# hitpoint.net
KiCad netlist of a schematic drawn in EAGLE
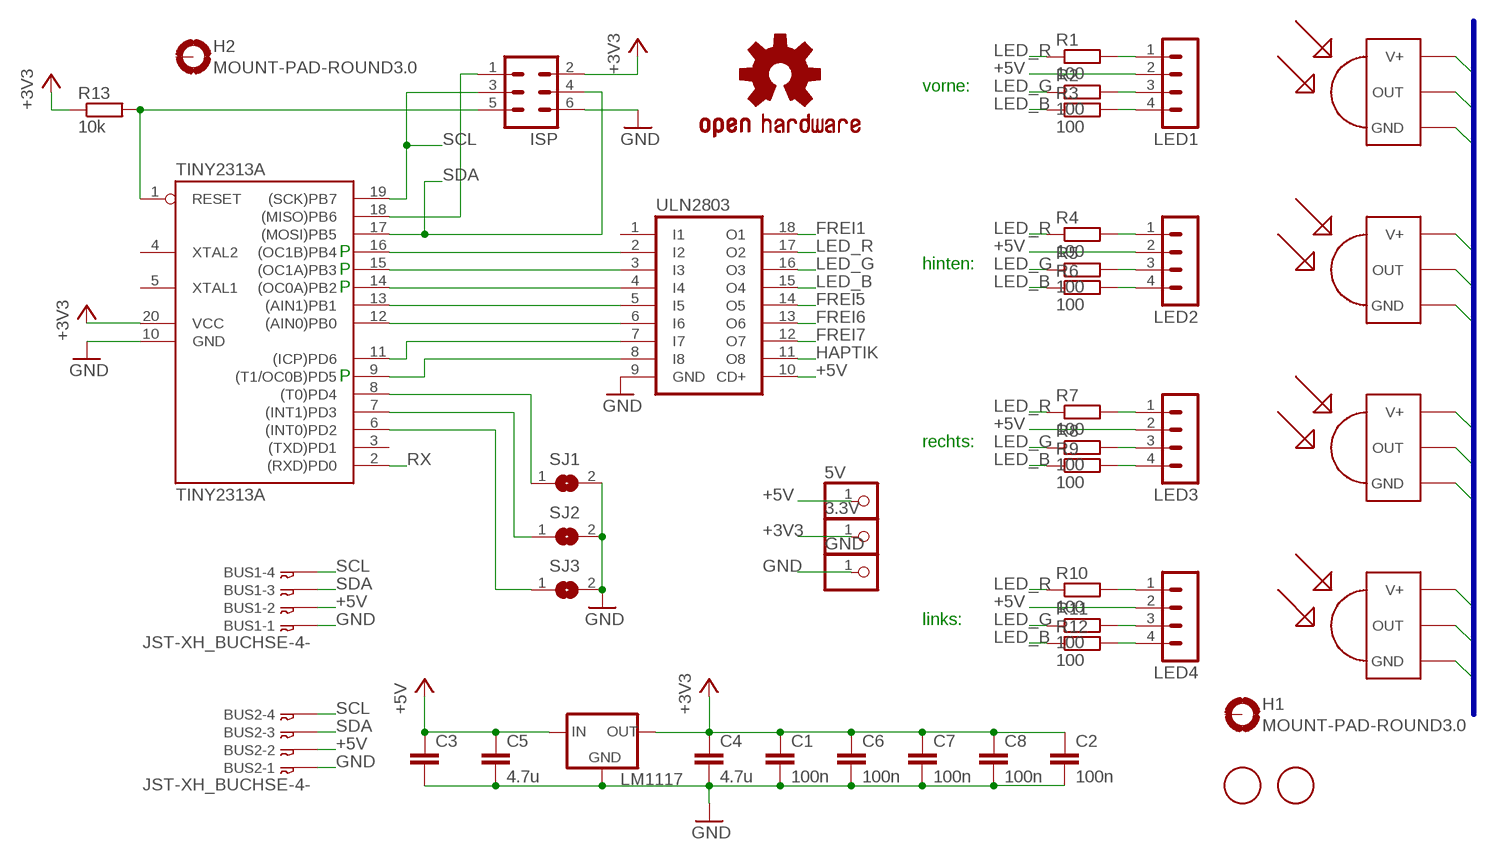
[diagram p0: schematic, sheet 1]

(export (version "E")
  (design (tool "Eeschema 10.0.6"))
  (components
    (comp (ref "3.3V")
      (value "PIN-HEADER-1")
      (footprint "eagle-import:PIN-HEADER-1")
      (libsource (lib "eagle-import") (part "PIN-HEADER-1"))
    )
    (comp (ref "5V")
      (value "PIN-HEADER-1")
      (footprint "eagle-import:PIN-HEADER-1")
      (libsource (lib "eagle-import") (part "PIN-HEADER-1"))
    )
    (comp (ref "BUS1")
      (value "JST-XH_BUCHSE-4-")
      (footprint "eagle-import:JST-XH_BUCHSE-4")
      (libsource (lib "eagle-import") (part "JST-XH_BUCHSE-4-"))
    )
    (comp (ref "BUS2")
      (value "JST-XH_BUCHSE-4-")
      (footprint "eagle-import:JST-XH_BUCHSE-4")
      (libsource (lib "eagle-import") (part "JST-XH_BUCHSE-4-"))
    )
    (comp (ref "C1")
      (value "100n")
      (footprint "eagle-import:0603")
      (libsource (lib "eagle-import") (part "C_EU0603"))
    )
    (comp (ref "C2")
      (value "100n")
      (footprint "eagle-import:0603")
      (libsource (lib "eagle-import") (part "C_EU0603"))
    )
    (comp (ref "C3")
      (value "C_EUCAP_UNIVERSAL")
      (footprint "eagle-import:C_UNIVERSAL")
      (libsource (lib "eagle-import") (part "C_EUCAP_UNIVERSAL"))
    )
    (comp (ref "C4")
      (value "4.7u")
      (footprint "eagle-import:0805")
      (libsource (lib "eagle-import") (part "C_EU0805"))
    )
    (comp (ref "C5")
      (value "4.7u")
      (footprint "eagle-import:0805")
      (libsource (lib "eagle-import") (part "C_EU0805"))
    )
    (comp (ref "C6")
      (value "100n")
      (footprint "eagle-import:0603")
      (libsource (lib "eagle-import") (part "C_EU0603"))
    )
    (comp (ref "C7")
      (value "100n")
      (footprint "eagle-import:0603")
      (libsource (lib "eagle-import") (part "C_EU0603"))
    )
    (comp (ref "C8")
      (value "100n")
      (footprint "eagle-import:0603")
      (libsource (lib "eagle-import") (part "C_EU0603"))
    )
    (comp (ref "GND")
      (value "PIN-HEADER-1")
      (footprint "eagle-import:PIN-HEADER-1")
      (libsource (lib "eagle-import") (part "PIN-HEADER-1"))
    )
    (comp (ref "H1")
      (value "MOUNT-PAD-ROUND3.0")
      (footprint "eagle-import:3,0-PAD")
      (libsource (lib "eagle-import") (part "MOUNT-PAD-ROUND3.0"))
    )
    (comp (ref "H2")
      (value "MOUNT-PAD-ROUND3.0")
      (footprint "eagle-import:3,0-PAD")
      (libsource (lib "eagle-import") (part "MOUNT-PAD-ROUND3.0"))
    )
    (comp (ref "ISP")
      (value "PIN-HEADER-3X2")
      (footprint "eagle-import:PIN-HEADER-3X2")
      (libsource (lib "eagle-import") (part "PIN-HEADER-3X2"))
    )
    (comp (ref "LED1")
      (value "PIN-HEADER-4")
      (footprint "eagle-import:PIN-HEADER-4")
      (libsource (lib "eagle-import") (part "PIN-HEADER-4"))
    )
    (comp (ref "LED2")
      (value "PIN-HEADER-4")
      (footprint "eagle-import:PIN-HEADER-4")
      (libsource (lib "eagle-import") (part "PIN-HEADER-4"))
    )
    (comp (ref "LED3")
      (value "PIN-HEADER-4")
      (footprint "eagle-import:PIN-HEADER-4")
      (libsource (lib "eagle-import") (part "PIN-HEADER-4"))
    )
    (comp (ref "LED4")
      (value "PIN-HEADER-4")
      (footprint "eagle-import:PIN-HEADER-4")
      (libsource (lib "eagle-import") (part "PIN-HEADER-4"))
    )
    (comp (ref "LM1117")
      (value "LM1117_3V3_REGULATOR")
      (footprint "eagle-import:SOT223")
      (libsource (lib "eagle-import") (part "LM1117_3V3_REGULATOR"))
    )
    (comp (ref "LOGO1")
      (value "OSHW-LOGOM")
      (footprint "eagle-import:OSHW-LOGO-M")
      (libsource (lib "eagle-import") (part "OSHW-LOGOM"))
    )
    (comp (ref "LOGO2")
      (value "OSHW-LOGOM")
      (footprint "eagle-import:OSHW-LOGO-M")
      (libsource (lib "eagle-import") (part "OSHW-LOGOM"))
    )
    (comp (ref "R1")
      (value "100")
      (footprint "eagle-import:0603")
      (libsource (lib "eagle-import") (part "R_EU0603"))
    )
    (comp (ref "R2")
      (value "100")
      (footprint "eagle-import:0603")
      (libsource (lib "eagle-import") (part "R_EU0603"))
    )
    (comp (ref "R3")
      (value "100")
      (footprint "eagle-import:0603")
      (libsource (lib "eagle-import") (part "R_EU0603"))
    )
    (comp (ref "R4")
      (value "100")
      (footprint "eagle-import:0603")
      (libsource (lib "eagle-import") (part "R_EU0603"))
    )
    (comp (ref "R5")
      (value "100")
      (footprint "eagle-import:0603")
      (libsource (lib "eagle-import") (part "R_EU0603"))
    )
    (comp (ref "R6")
      (value "100")
      (footprint "eagle-import:0603")
      (libsource (lib "eagle-import") (part "R_EU0603"))
    )
    (comp (ref "R7")
      (value "100")
      (footprint "eagle-import:0603")
      (libsource (lib "eagle-import") (part "R_EU0603"))
    )
    (comp (ref "R8")
      (value "100")
      (footprint "eagle-import:0603")
      (libsource (lib "eagle-import") (part "R_EU0603"))
    )
    (comp (ref "R9")
      (value "100")
      (footprint "eagle-import:0603")
      (libsource (lib "eagle-import") (part "R_EU0603"))
    )
    (comp (ref "R10")
      (value "100")
      (footprint "eagle-import:0603")
      (libsource (lib "eagle-import") (part "R_EU0603"))
    )
    (comp (ref "R11")
      (value "100")
      (footprint "eagle-import:0603")
      (libsource (lib "eagle-import") (part "R_EU0603"))
    )
    (comp (ref "R12")
      (value "100")
      (footprint "eagle-import:0603")
      (libsource (lib "eagle-import") (part "R_EU0603"))
    )
    (comp (ref "R13")
      (value "10k")
      (footprint "eagle-import:0603")
      (libsource (lib "eagle-import") (part "R_EU0603"))
    )
    (comp (ref "SJ1") (value "SJ") (footprint "eagle-import:SJ") (libsource (lib "eagle-import") (part "SJ")))
    (comp (ref "SJ2") (value "SJ") (footprint "eagle-import:SJ") (libsource (lib "eagle-import") (part "SJ")))
    (comp (ref "SJ3") (value "SJ") (footprint "eagle-import:SJ") (libsource (lib "eagle-import") (part "SJ")))
    (comp (ref "TINY2313A")
      (value "TINY2313A")
      (footprint "eagle-import:SO20LVERSTUMMELT")
      (libsource (lib "eagle-import") (part "TINY2313A"))
    )
    (comp (ref "U$1")
      (value "TSOP4338")
      (footprint "eagle-import:TSOP4338")
      (libsource (lib "eagle-import") (part "TSOP4338"))
    )
    (comp (ref "U$2")
      (value "TSOP4338")
      (footprint "eagle-import:TSOP4338")
      (libsource (lib "eagle-import") (part "TSOP4338"))
    )
    (comp (ref "U$3")
      (value "TSOP4338")
      (footprint "eagle-import:TSOP4338")
      (libsource (lib "eagle-import") (part "TSOP4338"))
    )
    (comp (ref "U$4")
      (value "TSOP4338")
      (footprint "eagle-import:TSOP4338")
      (libsource (lib "eagle-import") (part "TSOP4338"))
    )
    (comp (ref "U$5")
      (value "FIDUCIAL")
      (footprint "eagle-import:FIDUCIAL_1MM")
      (libsource (lib "eagle-import") (part "FIDUCIAL"))
    )
    (comp (ref "U$6")
      (value "FIDUCIAL")
      (footprint "eagle-import:FIDUCIAL_1MM")
      (libsource (lib "eagle-import") (part "FIDUCIAL"))
    )
    (comp (ref "ULN2803")
      (value "ULN2803ASO18")
      (footprint "eagle-import:SO18W")
      (libsource (lib "eagle-import") (part "ULN2803ASO18"))
    )
  )
  (nets
    (net (code "1") (name "+3V3") (class "Default")
      (node (ref "3.3V") (pin "1") (pinfunction "1_1") (pintype "passive"))
      (node (ref "C1") (pin "1") (pinfunction "1_1") (pintype "passive"))
      (node (ref "C2") (pin "1") (pinfunction "1_1") (pintype "passive"))
      (node (ref "C4") (pin "1") (pinfunction "1_1") (pintype "passive"))
      (node (ref "C6") (pin "1") (pinfunction "1_1") (pintype "passive"))
      (node (ref "C7") (pin "1") (pinfunction "1_1") (pintype "passive"))
      (node (ref "C8") (pin "1") (pinfunction "1_1") (pintype "passive"))
      (node (ref "ISP") (pin "2") (pinfunction "2_2") (pintype "passive"))
      (node (ref "LM1117") (pin "2") (pinfunction "OUT_2") (pintype "passive"))
      (node (ref "LM1117") (pin "4") (pinfunction "OUT_4") (pintype "passive"))
      (node (ref "R13") (pin "1") (pinfunction "1_1") (pintype "passive"))
      (node (ref "TINY2313A") (pin "20") (pinfunction "VCC_20") (pintype "power_in"))
      (node (ref "U$1") (pin "VCC") (pinfunction "V+_VCC") (pintype "bidirectional"))
      (node (ref "U$2") (pin "VCC") (pinfunction "V+_VCC") (pintype "bidirectional"))
      (node (ref "U$3") (pin "VCC") (pinfunction "V+_VCC") (pintype "bidirectional"))
      (node (ref "U$4") (pin "VCC") (pinfunction "V+_VCC") (pintype "bidirectional"))
    )
    (net (code "2") (name "+5V") (class "Default")
      (node (ref "5V") (pin "1") (pinfunction "1_1") (pintype "passive"))
      (node (ref "BUS1") (pin "P$2") (pinfunction "1_P$2") (pintype "passive"))
      (node (ref "BUS2") (pin "P$2") (pinfunction "1_P$2") (pintype "passive"))
      (node (ref "C3") (pin "1") (pinfunction "1_1") (pintype "passive"))
      (node (ref "C3") (pin "1B") (pinfunction "1_1B") (pintype "passive"))
      (node (ref "C5") (pin "1") (pinfunction "1_1") (pintype "passive"))
      (node (ref "LED1") (pin "2") (pinfunction "2_2") (pintype "passive"))
      (node (ref "LED2") (pin "2") (pinfunction "2_2") (pintype "passive"))
      (node (ref "LED3") (pin "2") (pinfunction "2_2") (pintype "passive"))
      (node (ref "LED4") (pin "2") (pinfunction "2_2") (pintype "passive"))
      (node (ref "LM1117") (pin "3") (pinfunction "IN_3") (pintype "input"))
      (node (ref "ULN2803") (pin "10") (pinfunction "CD+_10") (pintype "passive"))
    )
    (net (code "3") (name "/FREI1") (class "Default")
      (node (ref "ULN2803") (pin "18") (pinfunction "O1_18") (pintype "open_collector"))
    )
    (net (code "4") (name "/FREI5") (class "Default")
      (node (ref "ULN2803") (pin "14") (pinfunction "O5_14") (pintype "open_collector"))
    )
    (net (code "5") (name "/FREI6") (class "Default")
      (node (ref "ULN2803") (pin "13") (pinfunction "O6_13") (pintype "open_collector"))
    )
    (net (code "6") (name "/FREI7") (class "Default")
      (node (ref "ULN2803") (pin "12") (pinfunction "O7_12") (pintype "open_collector"))
    )
    (net (code "7") (name "/HAPTIK") (class "Default")
      (node (ref "ULN2803") (pin "11") (pinfunction "O8_11") (pintype "open_collector"))
    )
    (net (code "8") (name "/LED_B") (class "Default")
      (node (ref "R12") (pin "1") (pinfunction "1_1") (pintype "passive"))
      (node (ref "R3") (pin "1") (pinfunction "1_1") (pintype "passive"))
      (node (ref "R6") (pin "1") (pinfunction "1_1") (pintype "passive"))
      (node (ref "R9") (pin "1") (pinfunction "1_1") (pintype "passive"))
      (node (ref "ULN2803") (pin "15") (pinfunction "O4_15") (pintype "open_collector"))
    )
    (net (code "9") (name "/LED_G") (class "Default")
      (node (ref "R11") (pin "1") (pinfunction "1_1") (pintype "passive"))
      (node (ref "R2") (pin "1") (pinfunction "1_1") (pintype "passive"))
      (node (ref "R5") (pin "1") (pinfunction "1_1") (pintype "passive"))
      (node (ref "R8") (pin "1") (pinfunction "1_1") (pintype "passive"))
      (node (ref "ULN2803") (pin "16") (pinfunction "O3_16") (pintype "open_collector"))
    )
    (net (code "10") (name "/LED_R") (class "Default")
      (node (ref "R1") (pin "1") (pinfunction "1_1") (pintype "passive"))
      (node (ref "R10") (pin "1") (pinfunction "1_1") (pintype "passive"))
      (node (ref "R4") (pin "1") (pinfunction "1_1") (pintype "passive"))
      (node (ref "R7") (pin "1") (pinfunction "1_1") (pintype "passive"))
      (node (ref "ULN2803") (pin "17") (pinfunction "O2_17") (pintype "open_collector"))
    )
    (net (code "11") (name "/RX") (class "Default")
      (node (ref "TINY2313A") (pin "2") (pinfunction "(RXD)PD0_2") (pintype "bidirectional"))
      (node (ref "U$1") (pin "OUT") (pinfunction "OUT_OUT") (pintype "bidirectional"))
      (node (ref "U$2") (pin "OUT") (pinfunction "OUT_OUT") (pintype "bidirectional"))
      (node (ref "U$3") (pin "OUT") (pinfunction "OUT_OUT") (pintype "bidirectional"))
      (node (ref "U$4") (pin "OUT") (pinfunction "OUT_OUT") (pintype "bidirectional"))
    )
    (net (code "12") (name "/SCL") (class "Default")
      (node (ref "BUS1") (pin "P$4") (pinfunction "1_P$4") (pintype "passive"))
      (node (ref "BUS2") (pin "P$4") (pinfunction "1_P$4") (pintype "passive"))
      (node (ref "ISP") (pin "3") (pinfunction "3_3") (pintype "passive"))
      (node (ref "TINY2313A") (pin "19") (pinfunction "(SCK)PB7_19") (pintype "bidirectional"))
    )
    (net (code "13") (name "/SDA") (class "Default")
      (node (ref "BUS1") (pin "P$3") (pinfunction "1_P$3") (pintype "passive"))
      (node (ref "BUS2") (pin "P$3") (pinfunction "1_P$3") (pintype "passive"))
      (node (ref "ISP") (pin "4") (pinfunction "4_4") (pintype "passive"))
      (node (ref "TINY2313A") (pin "17") (pinfunction "(MOSI)PB5_17") (pintype "bidirectional"))
    )
    (net (code "14") (name "GND") (class "Default")
      (node (ref "BUS1") (pin "P$1") (pinfunction "1_P$1") (pintype "passive"))
      (node (ref "BUS2") (pin "P$1") (pinfunction "1_P$1") (pintype "passive"))
      (node (ref "C1") (pin "2") (pinfunction "2_2") (pintype "passive"))
      (node (ref "C2") (pin "2") (pinfunction "2_2") (pintype "passive"))
      (node (ref "C3") (pin "2") (pinfunction "2_2") (pintype "passive"))
      (node (ref "C3") (pin "2B") (pinfunction "2_2B") (pintype "passive"))
      (node (ref "C4") (pin "2") (pinfunction "2_2") (pintype "passive"))
      (node (ref "C5") (pin "2") (pinfunction "2_2") (pintype "passive"))
      (node (ref "C6") (pin "2") (pinfunction "2_2") (pintype "passive"))
      (node (ref "C7") (pin "2") (pinfunction "2_2") (pintype "passive"))
      (node (ref "C8") (pin "2") (pinfunction "2_2") (pintype "passive"))
      (node (ref "GND") (pin "1") (pinfunction "1_1") (pintype "passive"))
      (node (ref "ISP") (pin "6") (pinfunction "6_6") (pintype "passive"))
      (node (ref "LM1117") (pin "1") (pinfunction "GND_1") (pintype "input"))
      (node (ref "SJ1") (pin "2") (pinfunction "2_2") (pintype "passive"))
      (node (ref "SJ2") (pin "2") (pinfunction "2_2") (pintype "passive"))
      (node (ref "SJ3") (pin "2") (pinfunction "2_2") (pintype "passive"))
      (node (ref "TINY2313A") (pin "10") (pinfunction "GND_10") (pintype "power_in"))
      (node (ref "U$1") (pin "GND") (pinfunction "GND_GND") (pintype "bidirectional"))
      (node (ref "U$2") (pin "GND") (pinfunction "GND_GND") (pintype "bidirectional"))
      (node (ref "U$3") (pin "GND") (pinfunction "GND_GND") (pintype "bidirectional"))
      (node (ref "U$4") (pin "GND") (pinfunction "GND_GND") (pintype "bidirectional"))
      (node (ref "ULN2803") (pin "9") (pinfunction "GND_9") (pintype "power_in"))
    )
    (net (code "15") (name "Net-(LED1-Pad1)") (class "Default")
      (node (ref "LED1") (pin "1") (pinfunction "1_1") (pintype "passive"))
      (node (ref "R1") (pin "2") (pinfunction "2_2") (pintype "passive"))
    )
    (net (code "16") (name "Net-(LED1-Pad3)") (class "Default")
      (node (ref "LED1") (pin "3") (pinfunction "3_3") (pintype "passive"))
      (node (ref "R2") (pin "2") (pinfunction "2_2") (pintype "passive"))
    )
    (net (code "17") (name "Net-(LED1-Pad4)") (class "Default")
      (node (ref "LED1") (pin "4") (pinfunction "4_4") (pintype "passive"))
      (node (ref "R3") (pin "2") (pinfunction "2_2") (pintype "passive"))
    )
    (net (code "18") (name "Net-(LED2-Pad1)") (class "Default")
      (node (ref "LED2") (pin "1") (pinfunction "1_1") (pintype "passive"))
      (node (ref "R4") (pin "2") (pinfunction "2_2") (pintype "passive"))
    )
    (net (code "19") (name "Net-(LED2-Pad3)") (class "Default")
      (node (ref "LED2") (pin "3") (pinfunction "3_3") (pintype "passive"))
      (node (ref "R5") (pin "2") (pinfunction "2_2") (pintype "passive"))
    )
    (net (code "20") (name "Net-(LED2-Pad4)") (class "Default")
      (node (ref "LED2") (pin "4") (pinfunction "4_4") (pintype "passive"))
      (node (ref "R6") (pin "2") (pinfunction "2_2") (pintype "passive"))
    )
    (net (code "21") (name "Net-(LED3-Pad1)") (class "Default")
      (node (ref "LED3") (pin "1") (pinfunction "1_1") (pintype "passive"))
      (node (ref "R7") (pin "2") (pinfunction "2_2") (pintype "passive"))
    )
    (net (code "22") (name "Net-(LED3-Pad3)") (class "Default")
      (node (ref "LED3") (pin "3") (pinfunction "3_3") (pintype "passive"))
      (node (ref "R8") (pin "2") (pinfunction "2_2") (pintype "passive"))
    )
    (net (code "23") (name "Net-(LED3-Pad4)") (class "Default")
      (node (ref "LED3") (pin "4") (pinfunction "4_4") (pintype "passive"))
      (node (ref "R9") (pin "2") (pinfunction "2_2") (pintype "passive"))
    )
    (net (code "24") (name "Net-(LED4-Pad1)") (class "Default")
      (node (ref "LED4") (pin "1") (pinfunction "1_1") (pintype "passive"))
      (node (ref "R10") (pin "2") (pinfunction "2_2") (pintype "passive"))
    )
    (net (code "25") (name "Net-(LED4-Pad3)") (class "Default")
      (node (ref "LED4") (pin "3") (pinfunction "3_3") (pintype "passive"))
      (node (ref "R11") (pin "2") (pinfunction "2_2") (pintype "passive"))
    )
    (net (code "26") (name "Net-(LED4-Pad4)") (class "Default")
      (node (ref "LED4") (pin "4") (pinfunction "4_4") (pintype "passive"))
      (node (ref "R12") (pin "2") (pinfunction "2_2") (pintype "passive"))
    )
    (net (code "27") (name "Net-(TINY2313A-(AIN0)PB0)") (class "Default")
      (node (ref "TINY2313A") (pin "12") (pinfunction "(AIN0)PB0_12") (pintype "bidirectional"))
      (node (ref "ULN2803") (pin "6") (pinfunction "I6_6") (pintype "input"))
    )
    (net (code "28") (name "Net-(TINY2313A-(AIN1)PB1)") (class "Default")
      (node (ref "TINY2313A") (pin "13") (pinfunction "(AIN1)PB1_13") (pintype "bidirectional"))
      (node (ref "ULN2803") (pin "5") (pinfunction "I5_5") (pintype "input"))
    )
    (net (code "29") (name "Net-(TINY2313A-(ICP)PD6)") (class "Default")
      (node (ref "TINY2313A") (pin "11") (pinfunction "(ICP)PD6_11") (pintype "bidirectional"))
      (node (ref "ULN2803") (pin "7") (pinfunction "I7_7") (pintype "input"))
    )
    (net (code "30") (name "Net-(TINY2313A-(INT0)PD2)") (class "Default")
      (node (ref "SJ3") (pin "1") (pinfunction "1_1") (pintype "passive"))
      (node (ref "TINY2313A") (pin "6") (pinfunction "(INT0)PD2_6") (pintype "bidirectional"))
    )
    (net (code "31") (name "Net-(TINY2313A-(INT1)PD3)") (class "Default")
      (node (ref "SJ2") (pin "1") (pinfunction "1_1") (pintype "passive"))
      (node (ref "TINY2313A") (pin "7") (pinfunction "(INT1)PD3_7") (pintype "bidirectional"))
    )
    (net (code "32") (name "Net-(TINY2313A-(MISO)PB6)") (class "Default")
      (node (ref "ISP") (pin "1") (pinfunction "1_1") (pintype "passive"))
      (node (ref "TINY2313A") (pin "18") (pinfunction "(MISO)PB6_18") (pintype "bidirectional"))
    )
    (net (code "33") (name "Net-(TINY2313A-(OC0A)PB2)") (class "Default")
      (node (ref "TINY2313A") (pin "14") (pinfunction "(OC0A)PB2_14") (pintype "bidirectional"))
      (node (ref "ULN2803") (pin "4") (pinfunction "I4_4") (pintype "input"))
    )
    (net (code "34") (name "Net-(TINY2313A-(OC1A)PB3)") (class "Default")
      (node (ref "TINY2313A") (pin "15") (pinfunction "(OC1A)PB3_15") (pintype "bidirectional"))
      (node (ref "ULN2803") (pin "3") (pinfunction "I3_3") (pintype "input"))
    )
    (net (code "35") (name "Net-(TINY2313A-(OC1B)PB4)") (class "Default")
      (node (ref "TINY2313A") (pin "16") (pinfunction "(OC1B)PB4_16") (pintype "bidirectional"))
      (node (ref "ULN2803") (pin "2") (pinfunction "I2_2") (pintype "input"))
    )
    (net (code "36") (name "Net-(TINY2313A-(T0)PD4)") (class "Default")
      (node (ref "SJ1") (pin "1") (pinfunction "1_1") (pintype "passive"))
      (node (ref "TINY2313A") (pin "8") (pinfunction "(T0)PD4_8") (pintype "bidirectional"))
    )
    (net (code "37") (name "Net-(TINY2313A-(T1{slash}OC0B)PD5)") (class "Default")
      (node (ref "TINY2313A") (pin "9") (pinfunction "(T1/OC0B)PD5_9") (pintype "bidirectional"))
      (node (ref "ULN2803") (pin "8") (pinfunction "I8_8") (pintype "input"))
    )
    (net (code "38") (name "Net-(TINY2313A-RESET)") (class "Default")
      (node (ref "ISP") (pin "5") (pinfunction "5_5") (pintype "passive"))
      (node (ref "R13") (pin "2") (pinfunction "2_2") (pintype "passive"))
      (node (ref "TINY2313A") (pin "1") (pinfunction "RESET_1") (pintype "bidirectional"))
    )
    (net (code "39") (name "unconnected-(H1-MOUNT-PadB3,0)") (class "Default")
      (node (ref "H1") (pin "B3,0") (pinfunction "MOUNT_B3,0") (pintype "passive"))
    )
    (net (code "40") (name "unconnected-(H2-MOUNT-PadB3,0)") (class "Default")
      (node (ref "H2") (pin "B3,0") (pinfunction "MOUNT_B3,0") (pintype "passive"))
    )
    (net (code "41") (name "unconnected-(TINY2313A-(TXD)PD1-Pad3)") (class "Default")
      (node (ref "TINY2313A") (pin "3") (pinfunction "(TXD)PD1_3") (pintype "bidirectional"))
    )
    (net (code "42") (name "unconnected-(TINY2313A-XTAL1-Pad5)") (class "Default")
      (node (ref "TINY2313A") (pin "5") (pinfunction "XTAL1_5") (pintype "bidirectional"))
    )
    (net (code "43") (name "unconnected-(TINY2313A-XTAL2-Pad4)") (class "Default")
      (node (ref "TINY2313A") (pin "4") (pinfunction "XTAL2_4") (pintype "bidirectional"))
    )
    (net (code "44") (name "unconnected-(ULN2803-I1-Pad1)") (class "Default")
      (node (ref "ULN2803") (pin "1") (pinfunction "I1_1") (pintype "input"))
    )
  )
)
